# top.net
KiCad netlist of a schematic drawn in Altium Designer
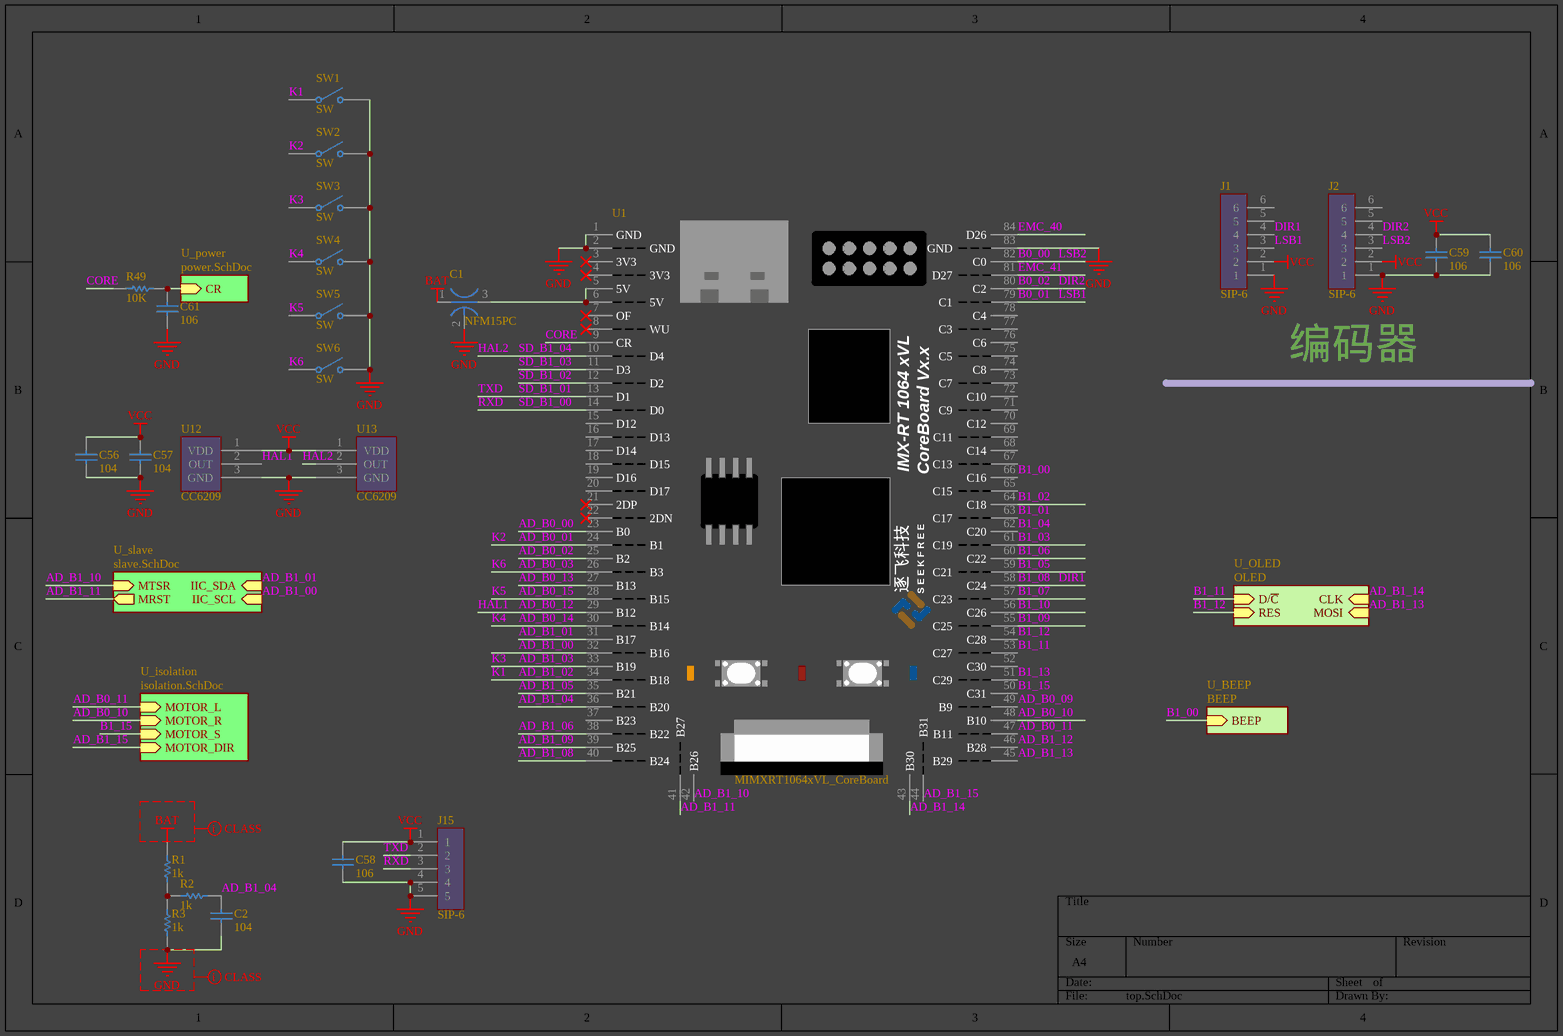
[diagram p0: top.SchDoc]

(export (version "E")
  (design (tool "Eeschema 10.0.6"))
  (components
    (comp (ref "C1")
      (value "NFM15PC")
      (footprint "FILTER-SMD_3P-L1.0-W0.5-L")
      (fields
        (field (name "BOM_SUPPLIER PART") "C162672")
        (field (name "BOM_MANUFACTURER PART") "NFM15PC473C1C3D")
        (field (name "CONTRIBUTOR") "LCSC")
      )
      (libsource (lib "iMag") (part "陶瓷滤波器"))
    )
    (comp (ref "C2")
      (value "104")
      (footprint "C0603")
      (description "Capacitor")
      (fields (field (name "PUBLISHER") "Altium Limited"))
      (libsource (lib "iMag") (part "电容"))
    )
    (comp (ref "C56")
      (value "104")
      (footprint "C0603")
      (description "Capacitor")
      (fields (field (name "PUBLISHER") "Altium Limited"))
      (libsource (lib "iMag") (part "电容"))
    )
    (comp (ref "C57")
      (value "104")
      (footprint "C0603")
      (description "Capacitor")
      (fields (field (name "PUBLISHER") "Altium Limited"))
      (libsource (lib "iMag") (part "电容"))
    )
    (comp (ref "C58")
      (value "106")
      (footprint "C0603")
      (description "Capacitor")
      (fields (field (name "PUBLISHER") "Altium Limited"))
      (libsource (lib "iMag") (part "电容"))
    )
    (comp (ref "C59")
      (value "106")
      (footprint "C0603")
      (description "Capacitor")
      (fields (field (name "PUBLISHER") "Altium Limited"))
      (libsource (lib "iMag") (part "电容"))
    )
    (comp (ref "C60")
      (value "106")
      (footprint "C0603")
      (description "Capacitor")
      (fields (field (name "PUBLISHER") "Altium Limited"))
      (libsource (lib "iMag") (part "电容"))
    )
    (comp (ref "C61")
      (value "106")
      (footprint "C0603")
      (description "Capacitor")
      (fields (field (name "PUBLISHER") "Altium Limited"))
      (libsource (lib "iMag") (part "电容"))
    )
    (comp (ref "J1") (value "SIP-6") (footprint "2.54简易牛角座6P") (libsource (lib "iMag") (part "SIP-6")))
    (comp (ref "J2") (value "SIP-6") (footprint "2.54简易牛角座6P") (libsource (lib "iMag") (part "SIP-6")))
    (comp (ref "J15") (value "SIP-6") (footprint "2.54排针1X5") (libsource (lib "iMag") (part "SIP-5")))
    (comp (ref "R1")
      (value "1k")
      (footprint "R0603")
      (description "Resistor")
      (fields (field (name "PUBLISHER") "Altium Limited"))
      (libsource (lib "iMag") (part "电阻"))
    )
    (comp (ref "R2")
      (value "1k")
      (footprint "R0603")
      (description "Resistor")
      (fields (field (name "PUBLISHER") "Altium Limited"))
      (libsource (lib "iMag") (part "电阻"))
    )
    (comp (ref "R3")
      (value "1k")
      (footprint "R0603")
      (description "Resistor")
      (fields (field (name "PUBLISHER") "Altium Limited"))
      (libsource (lib "iMag") (part "电阻"))
    )
    (comp (ref "R49")
      (value "10K")
      (footprint "R0603")
      (description "Resistor")
      (fields (field (name "PUBLISHER") "Altium Limited"))
      (libsource (lib "iMag") (part "电阻"))
    )
    (comp (ref "SW1")
      (value "SW")
      (footprint "KEY-SMD_4P-L4.2-W3.2-P2.20-LS4.6")
      (description "Single-Pole, Single-Throw Switch")
      (libsource (lib "iMag") (part "Switch"))
    )
    (comp (ref "SW2")
      (value "SW")
      (footprint "KEY-SMD_4P-L4.2-W3.2-P2.20-LS4.6")
      (description "Single-Pole, Single-Throw Switch")
      (libsource (lib "iMag") (part "Switch"))
    )
    (comp (ref "SW3")
      (value "SW")
      (footprint "KEY-SMD_4P-L4.2-W3.2-P2.20-LS4.6")
      (description "Single-Pole, Single-Throw Switch")
      (libsource (lib "iMag") (part "Switch"))
    )
    (comp (ref "SW4")
      (value "SW")
      (footprint "KEY-SMD_4P-L4.2-W3.2-P2.20-LS4.6")
      (description "Single-Pole, Single-Throw Switch")
      (libsource (lib "iMag") (part "Switch"))
    )
    (comp (ref "SW5")
      (value "SW")
      (footprint "KEY-SMD_4P-L4.2-W3.2-P2.20-LS4.6")
      (description "Single-Pole, Single-Throw Switch")
      (libsource (lib "iMag") (part "Switch"))
    )
    (comp (ref "SW6")
      (value "SW")
      (footprint "KEY-SMD_4P-L4.2-W3.2-P2.20-LS4.6")
      (description "Single-Pole, Single-Throw Switch")
      (libsource (lib "iMag") (part "Switch"))
    )
    (comp (ref "U1")
      (value "MIMXRT1064xVL_CoreBoard")
      (footprint "MIMXRT1064xVL_CoreBoard")
      (description "逐飞科技i.MX RT1064核心板整体原理，可直接使用")
      (libsource (lib "iMag") (part "MIMXRT1064xVL_CoreBoard"))
    )
    (comp (ref "U12") (value "CC6209") (footprint "SOT-23") (libsource (lib "iMag") (part "霍尔开关")))
    (comp (ref "U13") (value "CC6209") (footprint "SOT-23") (libsource (lib "") (part "霍尔开关_1")))
  )
  (nets
    (net (code "1") (name "/AD_B0_00") (class "Default")
      (node (ref "U1") (pin "23") (pinfunction "B0_23") (pintype "passive"))
    )
    (net (code "2") (name "/AD_B0_01") (class "Default")
      (node (ref "SW2") (pin "1") (pinfunction "COMMON_1") (pintype "passive"))
      (node (ref "U1") (pin "24") (pinfunction "B1_24") (pintype "passive"))
    )
    (net (code "3") (name "/AD_B0_02") (class "Default")
      (node (ref "U1") (pin "25") (pinfunction "B2_25") (pintype "passive"))
    )
    (net (code "4") (name "/AD_B0_03") (class "Default")
      (node (ref "SW6") (pin "1") (pinfunction "COMMON_1") (pintype "passive"))
      (node (ref "U1") (pin "26") (pinfunction "B3_26") (pintype "passive"))
    )
    (net (code "5") (name "/AD_B0_09") (class "Default")
      (node (ref "U1") (pin "49") (pinfunction "B9_49") (pintype "passive"))
    )
    (net (code "6") (name "/AD_B0_10") (class "Default")
      (node (ref "U1") (pin "48") (pinfunction "B10_48") (pintype "passive"))
    )
    (net (code "7") (name "/AD_B0_11") (class "Default")
      (node (ref "U1") (pin "47") (pinfunction "B11_47") (pintype "passive"))
    )
    (net (code "8") (name "/AD_B0_12") (class "Default")
      (node (ref "U1") (pin "29") (pinfunction "B12_29") (pintype "passive"))
      (node (ref "U12") (pin "2") (pinfunction "OUT_2") (pintype "passive"))
    )
    (net (code "9") (name "/AD_B0_13") (class "Default")
      (node (ref "U1") (pin "27") (pinfunction "B13_27") (pintype "passive"))
    )
    (net (code "10") (name "/AD_B0_14") (class "Default")
      (node (ref "SW4") (pin "1") (pinfunction "COMMON_1") (pintype "passive"))
      (node (ref "U1") (pin "30") (pinfunction "B14_30") (pintype "passive"))
    )
    (net (code "11") (name "/AD_B0_15") (class "Default")
      (node (ref "SW5") (pin "1") (pinfunction "COMMON_1") (pintype "passive"))
      (node (ref "U1") (pin "28") (pinfunction "B15_28") (pintype "passive"))
    )
    (net (code "12") (name "/AD_B1_00") (class "Default")
      (node (ref "U1") (pin "32") (pinfunction "B16_32") (pintype "passive"))
    )
    (net (code "13") (name "/AD_B1_01") (class "Default")
      (node (ref "U1") (pin "31") (pinfunction "B17_31") (pintype "passive"))
    )
    (net (code "14") (name "/AD_B1_02") (class "Default")
      (node (ref "SW1") (pin "1") (pinfunction "COMMON_1") (pintype "passive"))
      (node (ref "U1") (pin "34") (pinfunction "B18_34") (pintype "passive"))
    )
    (net (code "15") (name "/AD_B1_03") (class "Default")
      (node (ref "SW3") (pin "1") (pinfunction "COMMON_1") (pintype "passive"))
      (node (ref "U1") (pin "33") (pinfunction "B19_33") (pintype "passive"))
    )
    (net (code "16") (name "/AD_B1_04") (class "Default")
      (node (ref "C2") (pin "2") (pinfunction "2_2") (pintype "passive"))
      (node (ref "R2") (pin "1") (pinfunction "1_1") (pintype "passive"))
      (node (ref "U1") (pin "36") (pinfunction "B20_36") (pintype "passive"))
    )
    (net (code "17") (name "/AD_B1_05") (class "Default")
      (node (ref "U1") (pin "35") (pinfunction "B21_35") (pintype "passive"))
    )
    (net (code "18") (name "/AD_B1_06") (class "Default")
      (node (ref "U1") (pin "38") (pinfunction "B22_38") (pintype "passive"))
    )
    (net (code "19") (name "/AD_B1_08") (class "Default")
      (node (ref "U1") (pin "40") (pinfunction "B24_40") (pintype "passive"))
    )
    (net (code "20") (name "/AD_B1_09") (class "Default")
      (node (ref "U1") (pin "39") (pinfunction "B25_39") (pintype "passive"))
    )
    (net (code "21") (name "/AD_B1_10") (class "Default")
      (node (ref "U1") (pin "42") (pinfunction "B26_42") (pintype "passive"))
    )
    (net (code "22") (name "/AD_B1_11") (class "Default")
      (node (ref "U1") (pin "41") (pinfunction "B27_41") (pintype "passive"))
    )
    (net (code "23") (name "/AD_B1_12") (class "Default")
      (node (ref "U1") (pin "46") (pinfunction "B28_46") (pintype "passive"))
    )
    (net (code "24") (name "/AD_B1_13") (class "Default")
      (node (ref "U1") (pin "45") (pinfunction "B29_45") (pintype "passive"))
    )
    (net (code "25") (name "/AD_B1_14") (class "Default")
      (node (ref "U1") (pin "43") (pinfunction "B30_43") (pintype "passive"))
    )
    (net (code "26") (name "/AD_B1_15") (class "Default")
      (node (ref "U1") (pin "44") (pinfunction "B31_44") (pintype "passive"))
    )
    (net (code "27") (name "/B0_00") (class "Default")
      (node (ref "J2") (pin "3") (pinfunction "3_3") (pintype "passive"))
      (node (ref "U1") (pin "82") (pinfunction "C0_82") (pintype "passive"))
    )
    (net (code "28") (name "/B0_01") (class "Default")
      (node (ref "J1") (pin "3") (pinfunction "3_3") (pintype "passive"))
      (node (ref "U1") (pin "79") (pinfunction "C1_79") (pintype "passive"))
    )
    (net (code "29") (name "/B0_02") (class "Default")
      (node (ref "J2") (pin "4") (pinfunction "4_4") (pintype "passive"))
      (node (ref "U1") (pin "80") (pinfunction "C2_80") (pintype "passive"))
    )
    (net (code "30") (name "/B1_00") (class "Default")
      (node (ref "U1") (pin "66") (pinfunction "C16_66") (pintype "passive"))
    )
    (net (code "31") (name "/B1_01") (class "Default")
      (node (ref "U1") (pin "63") (pinfunction "C17_63") (pintype "passive"))
    )
    (net (code "32") (name "/B1_02") (class "Default")
      (node (ref "U1") (pin "64") (pinfunction "C18_64") (pintype "passive"))
    )
    (net (code "33") (name "/B1_03") (class "Default")
      (node (ref "U1") (pin "61") (pinfunction "C19_61") (pintype "passive"))
    )
    (net (code "34") (name "/B1_04") (class "Default")
      (node (ref "U1") (pin "62") (pinfunction "C20_62") (pintype "passive"))
    )
    (net (code "35") (name "/B1_05") (class "Default")
      (node (ref "U1") (pin "59") (pinfunction "C21_59") (pintype "passive"))
    )
    (net (code "36") (name "/B1_06") (class "Default")
      (node (ref "U1") (pin "60") (pinfunction "C22_60") (pintype "passive"))
    )
    (net (code "37") (name "/B1_07") (class "Default")
      (node (ref "U1") (pin "57") (pinfunction "C23_57") (pintype "passive"))
    )
    (net (code "38") (name "/B1_08") (class "Default")
      (node (ref "J1") (pin "4") (pinfunction "4_4") (pintype "passive"))
      (node (ref "U1") (pin "58") (pinfunction "C24_58") (pintype "passive"))
    )
    (net (code "39") (name "/B1_09") (class "Default")
      (node (ref "U1") (pin "55") (pinfunction "C25_55") (pintype "passive"))
    )
    (net (code "40") (name "/B1_10") (class "Default")
      (node (ref "U1") (pin "56") (pinfunction "C26_56") (pintype "passive"))
    )
    (net (code "41") (name "/B1_11") (class "Default")
      (node (ref "U1") (pin "53") (pinfunction "C27_53") (pintype "passive"))
    )
    (net (code "42") (name "/B1_12") (class "Default")
      (node (ref "U1") (pin "54") (pinfunction "C28_54") (pintype "passive"))
    )
    (net (code "43") (name "/B1_13") (class "Default")
      (node (ref "U1") (pin "51") (pinfunction "C29_51") (pintype "passive"))
    )
    (net (code "44") (name "/B1_15") (class "Default")
      (node (ref "U1") (pin "50") (pinfunction "C31_50") (pintype "passive"))
    )
    (net (code "45") (name "/CORE") (class "Default")
      (node (ref "R49") (pin "2") (pinfunction "2_2") (pintype "passive"))
      (node (ref "U1") (pin "9") (pinfunction "CR_9") (pintype "passive"))
    )
    (net (code "46") (name "/CR") (class "Default")
      (node (ref "C61") (pin "2") (pinfunction "2_2") (pintype "passive"))
      (node (ref "R49") (pin "1") (pinfunction "1_1") (pintype "passive"))
    )
    (net (code "47") (name "/EMC_40") (class "Default")
      (node (ref "U1") (pin "84") (pinfunction "D26_84") (pintype "passive"))
    )
    (net (code "48") (name "/EMC_41") (class "Default")
      (node (ref "U1") (pin "81") (pinfunction "D27_81") (pintype "passive"))
    )
    (net (code "49") (name "/HAL2") (class "Default")
      (node (ref "U1") (pin "10") (pinfunction "D4_10") (pintype "passive"))
      (node (ref "U13") (pin "2") (pinfunction "OUT_2") (pintype "passive"))
    )
    (net (code "50") (name "/RXD") (class "Default")
      (node (ref "J15") (pin "3") (pinfunction "3_3") (pintype "passive"))
      (node (ref "U1") (pin "14") (pinfunction "D0_14") (pintype "passive"))
    )
    (net (code "51") (name "/SD_B1_01") (class "Default")
      (node (ref "J15") (pin "2") (pinfunction "2_2") (pintype "passive"))
      (node (ref "U1") (pin "13") (pinfunction "D1_13") (pintype "passive"))
    )
    (net (code "52") (name "/SD_B1_02") (class "Default")
      (node (ref "U1") (pin "12") (pinfunction "D2_12") (pintype "passive"))
    )
    (net (code "53") (name "/SD_B1_03") (class "Default")
      (node (ref "U1") (pin "11") (pinfunction "D3_11") (pintype "passive"))
    )
    (net (code "54") (name "BAT") (class "Default")
      (node (ref "C1") (pin "1") (pinfunction "IN_1") (pintype "passive"))
      (node (ref "R1") (pin "2") (pinfunction "2_2") (pintype "passive"))
    )
    (net (code "55") (name "GND") (class "Default")
      (node (ref "C1") (pin "2") (pinfunction "GND_2") (pintype "passive"))
      (node (ref "C2") (pin "1") (pinfunction "1_1") (pintype "passive"))
      (node (ref "C56") (pin "1") (pinfunction "1_1") (pintype "passive"))
      (node (ref "C57") (pin "1") (pinfunction "1_1") (pintype "passive"))
      (node (ref "C58") (pin "1") (pinfunction "1_1") (pintype "passive"))
      (node (ref "C59") (pin "1") (pinfunction "1_1") (pintype "passive"))
      (node (ref "C60") (pin "1") (pinfunction "1_1") (pintype "passive"))
      (node (ref "C61") (pin "1") (pinfunction "1_1") (pintype "passive"))
      (node (ref "J1") (pin "1") (pinfunction "1_1") (pintype "passive"))
      (node (ref "J15") (pin "4") (pinfunction "4_4") (pintype "passive"))
      (node (ref "J15") (pin "5") (pinfunction "5_5") (pintype "passive"))
      (node (ref "J2") (pin "1") (pinfunction "1_1") (pintype "passive"))
      (node (ref "R3") (pin "1") (pinfunction "1_1") (pintype "passive"))
      (node (ref "SW1") (pin "2") (pinfunction "NO_2") (pintype "passive"))
      (node (ref "SW2") (pin "2") (pinfunction "NO_2") (pintype "passive"))
      (node (ref "SW3") (pin "2") (pinfunction "NO_2") (pintype "passive"))
      (node (ref "SW4") (pin "2") (pinfunction "NO_2") (pintype "passive"))
      (node (ref "SW5") (pin "2") (pinfunction "NO_2") (pintype "passive"))
      (node (ref "SW6") (pin "2") (pinfunction "NO_2") (pintype "passive"))
      (node (ref "U1") (pin "1") (pinfunction "GND_1") (pintype "passive"))
      (node (ref "U1") (pin "2") (pinfunction "GND_2") (pintype "passive"))
      (node (ref "U1") (pin "83") (pinfunction "GND_83") (pintype "passive"))
      (node (ref "U12") (pin "3") (pinfunction "GND_3") (pintype "passive"))
      (node (ref "U13") (pin "3") (pinfunction "GND_3") (pintype "passive"))
    )
    (net (code "56") (name "Net-(C1-OUT)") (class "Default")
      (node (ref "C1") (pin "3") (pinfunction "OUT_3") (pintype "passive"))
      (node (ref "U1") (pin "5") (pinfunction "5V_5") (pintype "passive"))
      (node (ref "U1") (pin "6") (pinfunction "5V_6") (pintype "passive"))
    )
    (net (code "57") (name "Net-(R1-Pad1)") (class "Default")
      (node (ref "R1") (pin "1") (pinfunction "1_1") (pintype "passive"))
      (node (ref "R2") (pin "2") (pinfunction "2_2") (pintype "passive"))
      (node (ref "R3") (pin "2") (pinfunction "2_2") (pintype "passive"))
    )
    (net (code "58") (name "VCC") (class "Default")
      (node (ref "C56") (pin "2") (pinfunction "2_2") (pintype "passive"))
      (node (ref "C57") (pin "2") (pinfunction "2_2") (pintype "passive"))
      (node (ref "C58") (pin "2") (pinfunction "2_2") (pintype "passive"))
      (node (ref "C59") (pin "2") (pinfunction "2_2") (pintype "passive"))
      (node (ref "C60") (pin "2") (pinfunction "2_2") (pintype "passive"))
      (node (ref "J1") (pin "2") (pinfunction "2_2") (pintype "passive"))
      (node (ref "J15") (pin "1") (pinfunction "1_1") (pintype "passive"))
      (node (ref "J2") (pin "2") (pinfunction "2_2") (pintype "passive"))
      (node (ref "U12") (pin "1") (pinfunction "VDD_1") (pintype "passive"))
      (node (ref "U13") (pin "1") (pinfunction "VDD_1") (pintype "passive"))
    )
    (net (code "59") (name "unconnected-(J1-Pad5)") (class "Default")
      (node (ref "J1") (pin "5") (pinfunction "5_5") (pintype "passive"))
    )
    (net (code "60") (name "unconnected-(J1-Pad6)") (class "Default")
      (node (ref "J1") (pin "6") (pinfunction "6_6") (pintype "passive"))
    )
    (net (code "61") (name "unconnected-(J2-Pad5)") (class "Default")
      (node (ref "J2") (pin "5") (pinfunction "5_5") (pintype "passive"))
    )
    (net (code "62") (name "unconnected-(J2-Pad6)") (class "Default")
      (node (ref "J2") (pin "6") (pinfunction "6_6") (pintype "passive"))
    )
    (net (code "63") (name "unconnected-(U1-2DN-Pad22)") (class "Default")
      (node (ref "U1") (pin "22") (pinfunction "2DN_22") (pintype "passive+no_connect"))
    )
    (net (code "64") (name "unconnected-(U1-2DP-Pad21)") (class "Default")
      (node (ref "U1") (pin "21") (pinfunction "2DP_21") (pintype "passive+no_connect"))
    )
    (net (code "65") (name "unconnected-(U1-3V3-Pad3)") (class "Default")
      (node (ref "U1") (pin "3") (pinfunction "3V3_3") (pintype "passive+no_connect"))
    )
    (net (code "66") (name "unconnected-(U1-3V3-Pad4)") (class "Default")
      (node (ref "U1") (pin "4") (pinfunction "3V3_4") (pintype "passive+no_connect"))
    )
    (net (code "67") (name "unconnected-(U1-B23-Pad37)") (class "Default")
      (node (ref "U1") (pin "37") (pinfunction "B23_37") (pintype "passive"))
    )
    (net (code "68") (name "unconnected-(U1-C3-Pad77)") (class "Default")
      (node (ref "U1") (pin "77") (pinfunction "C3_77") (pintype "passive"))
    )
    (net (code "69") (name "unconnected-(U1-C4-Pad78)") (class "Default")
      (node (ref "U1") (pin "78") (pinfunction "C4_78") (pintype "passive"))
    )
    (net (code "70") (name "unconnected-(U1-C5-Pad75)") (class "Default")
      (node (ref "U1") (pin "75") (pinfunction "C5_75") (pintype "passive"))
    )
    (net (code "71") (name "unconnected-(U1-C6-Pad76)") (class "Default")
      (node (ref "U1") (pin "76") (pinfunction "C6_76") (pintype "passive"))
    )
    (net (code "72") (name "unconnected-(U1-C7-Pad73)") (class "Default")
      (node (ref "U1") (pin "73") (pinfunction "C7_73") (pintype "passive"))
    )
    (net (code "73") (name "unconnected-(U1-C8-Pad74)") (class "Default")
      (node (ref "U1") (pin "74") (pinfunction "C8_74") (pintype "passive"))
    )
    (net (code "74") (name "unconnected-(U1-C9-Pad71)") (class "Default")
      (node (ref "U1") (pin "71") (pinfunction "C9_71") (pintype "passive"))
    )
    (net (code "75") (name "unconnected-(U1-C10-Pad72)") (class "Default")
      (node (ref "U1") (pin "72") (pinfunction "C10_72") (pintype "passive"))
    )
    (net (code "76") (name "unconnected-(U1-C11-Pad69)") (class "Default")
      (node (ref "U1") (pin "69") (pinfunction "C11_69") (pintype "passive"))
    )
    (net (code "77") (name "unconnected-(U1-C12-Pad70)") (class "Default")
      (node (ref "U1") (pin "70") (pinfunction "C12_70") (pintype "passive"))
    )
    (net (code "78") (name "unconnected-(U1-C13-Pad67)") (class "Default")
      (node (ref "U1") (pin "67") (pinfunction "C13_67") (pintype "passive"))
    )
    (net (code "79") (name "unconnected-(U1-C14-Pad68)") (class "Default")
      (node (ref "U1") (pin "68") (pinfunction "C14_68") (pintype "passive"))
    )
    (net (code "80") (name "unconnected-(U1-C15-Pad65)") (class "Default")
      (node (ref "U1") (pin "65") (pinfunction "C15_65") (pintype "passive"))
    )
    (net (code "81") (name "unconnected-(U1-C30-Pad52)") (class "Default")
      (node (ref "U1") (pin "52") (pinfunction "C30_52") (pintype "passive"))
    )
    (net (code "82") (name "unconnected-(U1-D12-Pad15)") (class "Default")
      (node (ref "U1") (pin "15") (pinfunction "D12_15") (pintype "passive"))
    )
    (net (code "83") (name "unconnected-(U1-D13-Pad16)") (class "Default")
      (node (ref "U1") (pin "16") (pinfunction "D13_16") (pintype "passive"))
    )
    (net (code "84") (name "unconnected-(U1-D14-Pad17)") (class "Default")
      (node (ref "U1") (pin "17") (pinfunction "D14_17") (pintype "passive"))
    )
    (net (code "85") (name "unconnected-(U1-D15-Pad18)") (class "Default")
      (node (ref "U1") (pin "18") (pinfunction "D15_18") (pintype "passive"))
    )
    (net (code "86") (name "unconnected-(U1-D16-Pad19)") (class "Default")
      (node (ref "U1") (pin "19") (pinfunction "D16_19") (pintype "passive"))
    )
    (net (code "87") (name "unconnected-(U1-D17-Pad20)") (class "Default")
      (node (ref "U1") (pin "20") (pinfunction "D17_20") (pintype "passive"))
    )
    (net (code "88") (name "unconnected-(U1-OF-Pad7)") (class "Default")
      (node (ref "U1") (pin "7") (pinfunction "OF_7") (pintype "passive+no_connect"))
    )
    (net (code "89") (name "unconnected-(U1-WU-Pad8)") (class "Default")
      (node (ref "U1") (pin "8") (pinfunction "WU_8") (pintype "passive+no_connect"))
    )
  )
)
